# 3V3-buck.net
KiCad netlist of a schematic drawn in Altium Designer
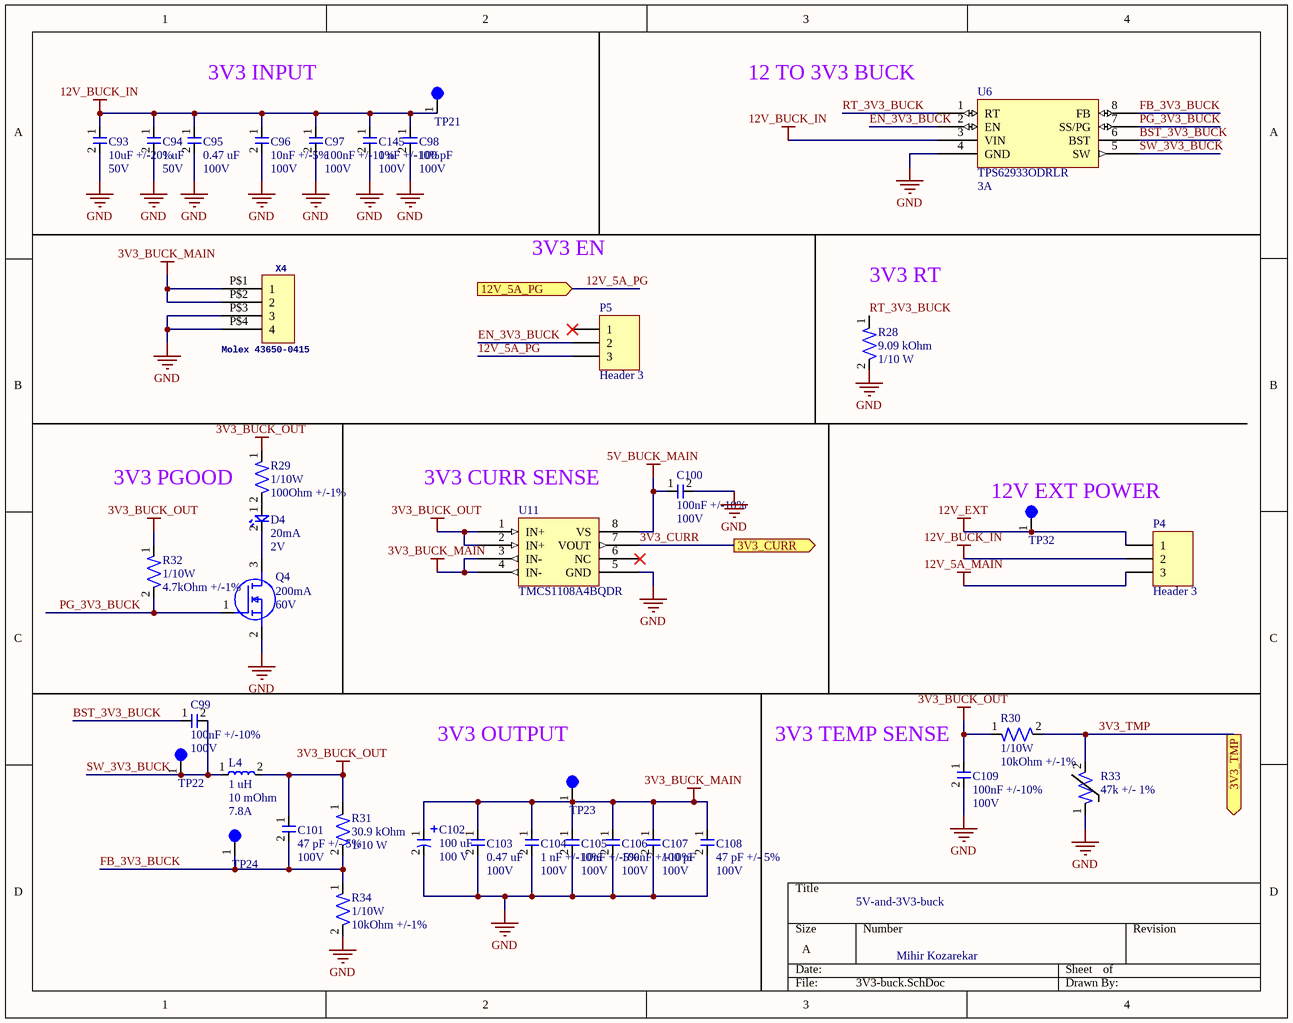
[diagram p0: 3V3-buck.SchDoc]

(export (version "E")
  (design (tool "Eeschema 10.0.6"))
  (components
    (comp (ref "C93")
      (value "CL31B106KBHNNNE")
      (footprint "CAP-1206")
      (description "10 µF ±10% 50V Ceramic Capacitor X7R 1206 (3216 Metric)")
      (fields
        (field (name "MANUFACTURER") "Samsung Electro-Mechanics")
        (field (name "CAPACITANCE") "10uF +/-20%")
        (field (name "VOLTAGE RATING") "50V")
      )
      (libsource (lib "MasterLib") (part "CAP-10U-0001"))
    )
    (comp (ref "C94")
      (value "UMK107AB7105KA-T")
      (footprint "CAP-0603")
      (description "1 µF ±10% 50V Ceramic Capacitor X7R 0603 (1608 Metric)")
      (fields (field (name "CAPACITANCE") "1 uF") (field (name "VOLTAGE") "50V"))
      (libsource (lib "MasterLib") (part "CAP-1U-0002"))
    )
    (comp (ref "C95")
      (value "KAM21KR72A474KL")
      (footprint "CAP-0805")
      (description "0.47 µF ±10% 100V Ceramic Capacitor X7R 0805 (2012 Metric)")
      (fields
        (field (name "TOLERANCE") "+/- 10%")
        (field (name "CAPACITANCE") "0.47 uF")
        (field (name "VOLTAGE") "100V")
      )
      (libsource (lib "MasterLib") (part "CAP-0.47U-0001"))
    )
    (comp (ref "C96")
      (value "C1608C0G2A103J080AC")
      (footprint "CAP-0603")
      (description "CAP CER 10000PF 100V C0G 0603")
      (fields
        (field (name "MANUFACTURER") "TDK Corporation")
        (field (name "CAPACITANCE") "10nF +/-5%")
        (field (name "VOLTAGE RATING") "100V")
      )
      (libsource (lib "MasterLib") (part "CAP-10N-0002"))
    )
    (comp (ref "C97")
      (value "CC0603KRX7R0BB104")
      (footprint "CAP-0603")
      (description "CAP CER 0.1UF 100V X7R 0603")
      (fields
        (field (name "MANUFACTURER") "YAGEO")
        (field (name "CAPACITANCE") "100nF +/-10%")
        (field (name "VOLTAGE RATING") "100V")
      )
      (libsource (lib "MasterLib") (part "CAP-100N-0001"))
    )
    (comp (ref "C98")
      (value "0603N101J101CT")
      (footprint "CAP-0603")
      (description "100 pF ±5% 100V Ceramic Capacitor C0G, NP0 0603 (1608 Metric)")
      (fields
        (field (name "TOLERANCE") "+/-5%")
        (field (name "CAPACITANCE") "100 pF")
        (field (name "VOLTAGE") "100V")
      )
      (libsource (lib "MasterLib") (part "CAP-100P-0002"))
    )
    (comp (ref "C99")
      (value "CC0603KRX7R0BB104")
      (footprint "CAP-0603")
      (description "CAP CER 0.1UF 100V X7R 0603")
      (fields
        (field (name "MANUFACTURER") "YAGEO")
        (field (name "CAPACITANCE") "100nF +/-10%")
        (field (name "VOLTAGE RATING") "100V")
      )
      (libsource (lib "MasterLib") (part "CAP-100N-0001"))
    )
    (comp (ref "C100")
      (value "CC0603KRX7R0BB104")
      (footprint "CAP-0603")
      (description "CAP CER 0.1UF 100V X7R 0603")
      (fields
        (field (name "MANUFACTURER") "YAGEO")
        (field (name "CAPACITANCE") "100nF +/-10%")
        (field (name "VOLTAGE RATING") "100V")
      )
      (libsource (lib "MasterLib") (part "CAP-100N-0001"))
    )
    (comp (ref "C101")
      (value "7447798111")
      (footprint "CAP-0603")
      (description "47 pF ±5% 100V Ceramic Capacitor C0G, NP0 0603 (1608 Metric)")
      (fields (field (name "CAPACITANCE") "47 pF +/- 5%") (field (name "VOLTAGE RATING") "100V"))
      (libsource (lib "MasterLib") (part "CAP-47P-0001"))
    )
    (comp (ref "C102")
      (value "100SEV100M12.5X16")
      (footprint "ELEC-100U-0001")
      (description "100 µF 100 V Aluminum Electrolytic Capacitors Radial, Can - SMD 2000 Hrs @ 85°C")
      (fields
        (field (name "MANUFACTURER") "Rubycon")
        (field (name "TOLERANCE") "+/- 20%")
        (field (name "CAPACITANCE") "100 uF")
        (field (name "VOLTAGE") "100 V")
      )
      (libsource (lib "MasterLib") (part "ELEC-100U-0001"))
    )
    (comp (ref "C103")
      (value "KAM21KR72A474KL")
      (footprint "CAP-0805")
      (description "0.47 µF ±10% 100V Ceramic Capacitor X7R 0805 (2012 Metric)")
      (fields
        (field (name "TOLERANCE") "+/- 10%")
        (field (name "CAPACITANCE") "0.47 uF")
        (field (name "VOLTAGE") "100V")
      )
      (libsource (lib "MasterLib") (part "CAP-0.47U-0001"))
    )
    (comp (ref "C104")
      (value "C0603Y102K1RAC7867")
      (footprint "CAP-0603")
      (description "1000 pF ±10% 100V Ceramic Capacitor X7R 0603 (1608 Metric)")
      (fields (field (name "CAPACITANCE") "1 nF +/-10%") (field (name "VOLTAGE") "100V"))
      (libsource (lib "MasterLib") (part "CAP-1N-0001"))
    )
    (comp (ref "C105")
      (value "C1608C0G2A103J080AC")
      (footprint "CAP-0603")
      (description "CAP CER 10000PF 100V C0G 0603")
      (fields
        (field (name "MANUFACTURER") "TDK Corporation")
        (field (name "CAPACITANCE") "10nF +/-5%")
        (field (name "VOLTAGE RATING") "100V")
      )
      (libsource (lib "MasterLib") (part "CAP-10N-0002"))
    )
    (comp (ref "C106")
      (value "CC0603KRX7R0BB104")
      (footprint "CAP-0603")
      (description "CAP CER 0.1UF 100V X7R 0603")
      (fields
        (field (name "MANUFACTURER") "YAGEO")
        (field (name "CAPACITANCE") "100nF +/-10%")
        (field (name "VOLTAGE RATING") "100V")
      )
      (libsource (lib "MasterLib") (part "CAP-100N-0001"))
    )
    (comp (ref "C107")
      (value "0603N101J101CT")
      (footprint "CAP-0603")
      (description "100 pF ±5% 100V Ceramic Capacitor C0G, NP0 0603 (1608 Metric)")
      (fields
        (field (name "TOLERANCE") "+/-5%")
        (field (name "CAPACITANCE") "100 pF")
        (field (name "VOLTAGE") "100V")
      )
      (libsource (lib "MasterLib") (part "CAP-100P-0002"))
    )
    (comp (ref "C108")
      (value "7447798111")
      (footprint "CAP-0603")
      (description "47 pF ±5% 100V Ceramic Capacitor C0G, NP0 0603 (1608 Metric)")
      (fields (field (name "CAPACITANCE") "47 pF +/- 5%") (field (name "VOLTAGE RATING") "100V"))
      (libsource (lib "MasterLib") (part "CAP-47P-0001"))
    )
    (comp (ref "C109")
      (value "CC0603KRX7R0BB104")
      (footprint "CAP-0603")
      (description "CAP CER 0.1UF 100V X7R 0603")
      (fields
        (field (name "MANUFACTURER") "YAGEO")
        (field (name "CAPACITANCE") "100nF +/-10%")
        (field (name "VOLTAGE RATING") "100V")
      )
      (libsource (lib "MasterLib") (part "CAP-100N-0001"))
    )
    (comp (ref "C145")
      (value "C0603Y102K1RAC7867")
      (footprint "CAP-0603")
      (description "1000 pF ±10% 100V Ceramic Capacitor X7R 0603 (1608 Metric)")
      (fields (field (name "CAPACITANCE") "1 nF +/-10%") (field (name "VOLTAGE") "100V"))
      (libsource (lib "MasterLib") (part "CAP-1N-0001"))
    )
    (comp (ref "D4")
      (value "150060AS75000")
      (footprint "LED-0603")
      (description "CAP CER 0.1UF 100V X7R 0603")
      (fields
        (field (name "MANUFACTURER") "Wurth Electronik")
        (field (name "CURRENT RATING") "20mA")
        (field (name "VF") "2V")
      )
      (libsource (lib "MasterLib") (part "LED_Amber_0001"))
    )
    (comp (ref "L4")
      (value "SRN8040-1R0Y")
      (footprint "PWRIND-6.8U-0001")
      (description "1 µH Semi-Shielded Drum Core, Wirewound Inductor 7.8 A 10mOhm Max Nonstandard")
      (fields
        (field (name "TOLERANCE") "30%")
        (field (name "INDUCTANCE") "1 uH")
        (field (name "DCR") "10 mOhm")
        (field (name "DCI") "7.8A")
      )
      (libsource (lib "MasterLib") (part "PWRIND-1U-0001"))
    )
    (comp (ref "P4")
      (value "Header 3")
      (footprint "HDR1X3")
      (description "Header, 3-Pin")
      (fields (field (name "PUBLISHER") "Altium Limited"))
      (libsource (lib "Miscellaneous Connectors") (part "Header 3"))
    )
    (comp (ref "P5")
      (value "Header 3")
      (footprint "HDR1X3")
      (description "Header, 3-Pin")
      (fields (field (name "PUBLISHER") "Altium Limited"))
      (libsource (lib "Miscellaneous Connectors") (part "Header 3"))
    )
    (comp (ref "Q4")
      (value "T2N7002AK,LM")
      (footprint "NMOS-SOT23-3")
      (description "MOSFET N-CH 60V 200MA SOT23")
      (fields
        (field (name "MANUFACTURER") "Toshiba")
        (field (name "ID-CONTINUOUS") "200mA")
        (field (name "VDS-MAX") "60V")
      )
      (libsource (lib "MasterLib") (part "NMOS-200MA-0001"))
    )
    (comp (ref "R28")
      (value "RC0603FR-079K09L")
      (footprint "RES-0603")
      (description "9.09 kOhms ±1% 0.1W, 1/10W Chip Resistor 0603 (1608 Metric) Moisture Resistant Thick Film")
      (fields
        (field (name "TOLERANCE") "+/-1%")
        (field (name "RESISTANCE") "9.09 kOhm")
        (field (name "POWER") "1/10 W")
      )
      (libsource (lib "MasterLib") (part "RES-9.09K-0001"))
    )
    (comp (ref "R29")
      (value "AC0603FR-10100RL")
      (footprint "RES-0603")
      (description "100 Ohms ±1% 0.1W, 1/10W Chip Resistor 0603 (1608 Metric) Automotive AEC-Q200 Thick Film")
      (fields
        (field (name "MANUFACTURER") "YAGEO")
        (field (name "POWER RATING") "1/10W")
        (field (name "RESISTANCE") "100Ohm +/-1%")
      )
      (libsource (lib "MasterLib") (part "RES-100-0002"))
    )
    (comp (ref "R30")
      (value "RC0603FR-0710KP")
      (footprint "RES-0603")
      (description "RES SMD 10K OHM 1% 1/10W 0603")
      (fields
        (field (name "MANUFACTURER") "YAGEO")
        (field (name "POWER RATING") "1/10W")
        (field (name "RESISTANCE") "10kOhm +/-1%")
      )
      (libsource (lib "MasterLib") (part "RES-10K-0002"))
    )
    (comp (ref "R31")
      (value "RC0603FR-0730K9L")
      (footprint "RES-0603")
      (description "30.9 kOhms ±1% 0.1W, 1/10W Chip Resistor 0603 (1608 Metric) Moisture Resistant Thick Film")
      (fields
        (field (name "TOLERANCE") "1%")
        (field (name "RESISTANCE") "30.9 kOhm")
        (field (name "POWER") "1/10 W")
      )
      (libsource (lib "MasterLib") (part "RES-30.9K-0001"))
    )
    (comp (ref "R32")
      (value "AF0603FR-074K7L")
      (footprint "RES-0603")
      (description "RES SMD 4.7K OHM 1% 1/10W 0603")
      (fields
        (field (name "MANUFACTURER") "YAGEO")
        (field (name "POWER RATING") "1/10W")
        (field (name "RESISTANCE") "4.7kOhm +/-1%")
      )
      (libsource (lib "MasterLib") (part "RES-4.7K-0002"))
    )
    (comp (ref "R33")
      (value "TMP6431DECR")
      (footprint "RES-0402")
      (description "PTC Thermistor 47 kOhms 0402 (1006 Metric)")
      (fields (field (name "MANUFACTURER") "Texas Instruments") (field (name "RESISTANCE") "47k +/- 1%"))
      (libsource (lib "MasterLib") (part "THERM-47K-0001"))
    )
    (comp (ref "R34")
      (value "RC0603FR-0710KP")
      (footprint "RES-0603")
      (description "RES SMD 10K OHM 1% 1/10W 0603")
      (fields
        (field (name "MANUFACTURER") "YAGEO")
        (field (name "POWER RATING") "1/10W")
        (field (name "RESISTANCE") "10kOhm +/-1%")
      )
      (libsource (lib "MasterLib") (part "RES-10K-0002"))
    )
    (comp (ref "TP21")
      (value "5003")
      (footprint "TEST-POINT-0001")
      (description "Oranange PC Test Point, Miniature Phoisphor Bronze Silver Plating Through Hole Mounting Type")
      (libsource (lib "MasterLib") (part "TEST-POINT-0001"))
    )
    (comp (ref "TP22")
      (value "5003")
      (footprint "TEST-POINT-0001")
      (description "Oranange PC Test Point, Miniature Phoisphor Bronze Silver Plating Through Hole Mounting Type")
      (libsource (lib "MasterLib") (part "TEST-POINT-0001"))
    )
    (comp (ref "TP23")
      (value "5003")
      (footprint "TEST-POINT-0001")
      (description "Oranange PC Test Point, Miniature Phoisphor Bronze Silver Plating Through Hole Mounting Type")
      (libsource (lib "MasterLib") (part "TEST-POINT-0001"))
    )
    (comp (ref "TP24")
      (value "5003")
      (footprint "TEST-POINT-0001")
      (description "Oranange PC Test Point, Miniature Phoisphor Bronze Silver Plating Through Hole Mounting Type")
      (libsource (lib "MasterLib") (part "TEST-POINT-0001"))
    )
    (comp (ref "TP32")
      (value "5003")
      (footprint "TEST-POINT-0001")
      (description "Oranange PC Test Point, Miniature Phoisphor Bronze Silver Plating Through Hole Mounting Type")
      (libsource (lib "MasterLib") (part "TEST-POINT-0001"))
    )
    (comp (ref "U6")
      (value "TPS62933ODRLR")
      (footprint "IC-SOT583")
      (description "Buck Switching Regulator IC Positive Adjustable 0.8V 1 Output 3A SOT-583")
      (fields (field (name "MANUFACTURER") "Texas Instruments") (field (name "CURRENT") "3A"))
      (libsource (lib "MasterLib") (part "IC-BUCK-0010"))
    )
    (comp (ref "U11")
      (value "TMCS1108A4BQDR")
      (footprint "IC-CURRENT-0001")
      (description "Current Sensor 1 Channel Hall Effect Bidirectional 8-SOIC (0.154\", 3.90mm Width)")
      (libsource (lib "MasterLib") (part "IC-CURRENT-0004"))
    )
    (comp (ref "X4")
      (value "Molex 43650-0415")
      (footprint "43650-0415")
      (libsource (lib "Molex Microfit") (part "Micro-Fit Molex 4 Pin Vertical"))
    )
  )
  (nets
    (net (code "1") (name "/3V3_CURR") (class "Default")
      (node (ref "U11") (pin "7") (pinfunction "VOUT_7") (pintype "output"))
    )
    (net (code "2") (name "/3V3_TMP") (class "Default")
      (node (ref "R30") (pin "2") (pinfunction "2_2") (pintype "passive"))
      (node (ref "R33") (pin "2") (pinfunction "2_2") (pintype "passive"))
    )
    (net (code "3") (name "/12V_5A_PG") (class "Default")
      (node (ref "P5") (pin "3") (pinfunction "3_3") (pintype "passive"))
    )
    (net (code "4") (name "/BST_3V3_BUCK") (class "Default")
      (node (ref "C99") (pin "1") (pinfunction "1_1") (pintype "passive"))
      (node (ref "U6") (pin "6") (pinfunction "BST_6") (pintype "power_in"))
    )
    (net (code "5") (name "/EN_3V3_BUCK") (class "Default")
      (node (ref "P5") (pin "2") (pinfunction "2_2") (pintype "passive"))
      (node (ref "U6") (pin "2") (pinfunction "EN_2") (pintype "bidirectional"))
    )
    (net (code "6") (name "/FB_3V3_BUCK") (class "Default")
      (node (ref "C101") (pin "2") (pinfunction "2_2") (pintype "passive"))
      (node (ref "R31") (pin "2") (pinfunction "2_2") (pintype "passive"))
      (node (ref "R34") (pin "1") (pinfunction "1_1") (pintype "passive"))
      (node (ref "TP24") (pin "1") (pinfunction "0_1") (pintype "passive"))
      (node (ref "U6") (pin "8") (pinfunction "FB_8") (pintype "bidirectional"))
    )
    (net (code "7") (name "/PG_3V3_BUCK") (class "Default")
      (node (ref "Q4") (pin "1") (pinfunction "G_1") (pintype "passive"))
      (node (ref "R32") (pin "2") (pinfunction "2_2") (pintype "passive"))
      (node (ref "U6") (pin "7") (pinfunction "SS/PG_7") (pintype "bidirectional"))
    )
    (net (code "8") (name "/RT_3V3_BUCK") (class "Default")
      (node (ref "R28") (pin "1") (pinfunction "1_1") (pintype "passive"))
      (node (ref "U6") (pin "1") (pinfunction "RT_1") (pintype "bidirectional"))
    )
    (net (code "9") (name "/SW_3V3_BUCK") (class "Default")
      (node (ref "C99") (pin "2") (pinfunction "2_2") (pintype "passive"))
      (node (ref "L4") (pin "1") (pinfunction "1_1") (pintype "passive"))
      (node (ref "TP22") (pin "1") (pinfunction "0_1") (pintype "passive"))
      (node (ref "U6") (pin "5") (pinfunction "SW_5") (pintype "output"))
    )
    (net (code "10") (name "3V3_BUCK_MAIN") (class "Default")
      (node (ref "C102") (pin "1") (pinfunction "1_1") (pintype "passive"))
      (node (ref "C103") (pin "1") (pinfunction "1_1") (pintype "passive"))
      (node (ref "C104") (pin "1") (pinfunction "1_1") (pintype "passive"))
      (node (ref "C105") (pin "1") (pinfunction "1_1") (pintype "passive"))
      (node (ref "C106") (pin "1") (pinfunction "1_1") (pintype "passive"))
      (node (ref "C107") (pin "1") (pinfunction "1_1") (pintype "passive"))
      (node (ref "C108") (pin "1") (pinfunction "1_1") (pintype "passive"))
      (node (ref "TP23") (pin "1") (pinfunction "0_1") (pintype "passive"))
      (node (ref "U11") (pin "3") (pinfunction "IN-_3") (pintype "output"))
      (node (ref "U11") (pin "4") (pinfunction "IN-_4") (pintype "output"))
      (node (ref "X4") (pin "P$1") (pinfunction "1_P$1") (pintype "passive"))
      (node (ref "X4") (pin "P$2") (pinfunction "2_P$2") (pintype "passive"))
    )
    (net (code "11") (name "3V3_BUCK_OUT") (class "Default")
      (node (ref "C101") (pin "1") (pinfunction "1_1") (pintype "passive"))
      (node (ref "C109") (pin "1") (pinfunction "1_1") (pintype "passive"))
      (node (ref "L4") (pin "2") (pinfunction "2_2") (pintype "passive"))
      (node (ref "R29") (pin "1") (pinfunction "1_1") (pintype "passive"))
      (node (ref "R30") (pin "1") (pinfunction "1_1") (pintype "passive"))
      (node (ref "R31") (pin "1") (pinfunction "1_1") (pintype "passive"))
      (node (ref "R32") (pin "1") (pinfunction "1_1") (pintype "passive"))
      (node (ref "U11") (pin "1") (pinfunction "IN+_1") (pintype "input"))
      (node (ref "U11") (pin "2") (pinfunction "IN+_2") (pintype "input"))
    )
    (net (code "12") (name "5V_BUCK_MAIN") (class "Default")
      (node (ref "C100") (pin "1") (pinfunction "1_1") (pintype "passive"))
      (node (ref "U11") (pin "8") (pinfunction "VS_8") (pintype "power_in"))
    )
    (net (code "13") (name "12V_5A_MAIN") (class "Default")
      (node (ref "P4") (pin "3") (pinfunction "3_3") (pintype "passive"))
    )
    (net (code "14") (name "12V_BUCK_IN") (class "Default")
      (node (ref "C145") (pin "1") (pinfunction "1_1") (pintype "passive"))
      (node (ref "C93") (pin "1") (pinfunction "1_1") (pintype "passive"))
      (node (ref "C94") (pin "1") (pinfunction "1_1") (pintype "passive"))
      (node (ref "C95") (pin "1") (pinfunction "1_1") (pintype "passive"))
      (node (ref "C96") (pin "1") (pinfunction "1_1") (pintype "passive"))
      (node (ref "C97") (pin "1") (pinfunction "1_1") (pintype "passive"))
      (node (ref "C98") (pin "1") (pinfunction "1_1") (pintype "passive"))
      (node (ref "P4") (pin "2") (pinfunction "2_2") (pintype "passive"))
      (node (ref "TP21") (pin "1") (pinfunction "0_1") (pintype "passive"))
      (node (ref "U6") (pin "3") (pinfunction "VIN_3") (pintype "power_in"))
    )
    (net (code "15") (name "12V_EXT") (class "Default")
      (node (ref "P4") (pin "1") (pinfunction "1_1") (pintype "passive"))
      (node (ref "TP32") (pin "1") (pinfunction "0_1") (pintype "passive"))
    )
    (net (code "16") (name "GND") (class "Default")
      (node (ref "C100") (pin "2") (pinfunction "2_2") (pintype "passive"))
      (node (ref "C102") (pin "2") (pinfunction "2_2") (pintype "passive"))
      (node (ref "C103") (pin "2") (pinfunction "2_2") (pintype "passive"))
      (node (ref "C104") (pin "2") (pinfunction "2_2") (pintype "passive"))
      (node (ref "C105") (pin "2") (pinfunction "2_2") (pintype "passive"))
      (node (ref "C106") (pin "2") (pinfunction "2_2") (pintype "passive"))
      (node (ref "C107") (pin "2") (pinfunction "2_2") (pintype "passive"))
      (node (ref "C108") (pin "2") (pinfunction "2_2") (pintype "passive"))
      (node (ref "C109") (pin "2") (pinfunction "2_2") (pintype "passive"))
      (node (ref "C145") (pin "2") (pinfunction "2_2") (pintype "passive"))
      (node (ref "C93") (pin "2") (pinfunction "2_2") (pintype "passive"))
      (node (ref "C94") (pin "2") (pinfunction "2_2") (pintype "passive"))
      (node (ref "C95") (pin "2") (pinfunction "2_2") (pintype "passive"))
      (node (ref "C96") (pin "2") (pinfunction "2_2") (pintype "passive"))
      (node (ref "C97") (pin "2") (pinfunction "2_2") (pintype "passive"))
      (node (ref "C98") (pin "2") (pinfunction "2_2") (pintype "passive"))
      (node (ref "Q4") (pin "2") (pinfunction "S_2") (pintype "passive"))
      (node (ref "R28") (pin "2") (pinfunction "2_2") (pintype "passive"))
      (node (ref "R33") (pin "1") (pinfunction "1_1") (pintype "passive"))
      (node (ref "R34") (pin "2") (pinfunction "2_2") (pintype "passive"))
      (node (ref "U11") (pin "5") (pinfunction "GND_5") (pintype "power_in"))
      (node (ref "U6") (pin "4") (pinfunction "GND_4") (pintype "power_in"))
      (node (ref "X4") (pin "P$3") (pinfunction "3_P$3") (pintype "passive"))
      (node (ref "X4") (pin "P$4") (pinfunction "4_P$4") (pintype "passive"))
    )
    (net (code "17") (name "Net-(D4-Pad1)") (class "Default")
      (node (ref "D4") (pin "1") (pinfunction "1_1") (pintype "passive"))
      (node (ref "R29") (pin "2") (pinfunction "2_2") (pintype "passive"))
    )
    (net (code "18") (name "Net-(Q4-D)") (class "Default")
      (node (ref "D4") (pin "2") (pinfunction "2_2") (pintype "passive"))
      (node (ref "Q4") (pin "3") (pinfunction "D_3") (pintype "passive"))
    )
    (net (code "19") (name "unconnected-(P5-Pad1)") (class "Default")
      (node (ref "P5") (pin "1") (pinfunction "1_1") (pintype "passive+no_connect"))
    )
    (net (code "20") (name "unconnected-(U11-NC-Pad6)") (class "Default")
      (node (ref "U11") (pin "6") (pinfunction "NC_6") (pintype "tri_state+no_connect"))
    )
  )
)
